# ospi_v14.net
KiCad netlist of a schematic drawn in EAGLE
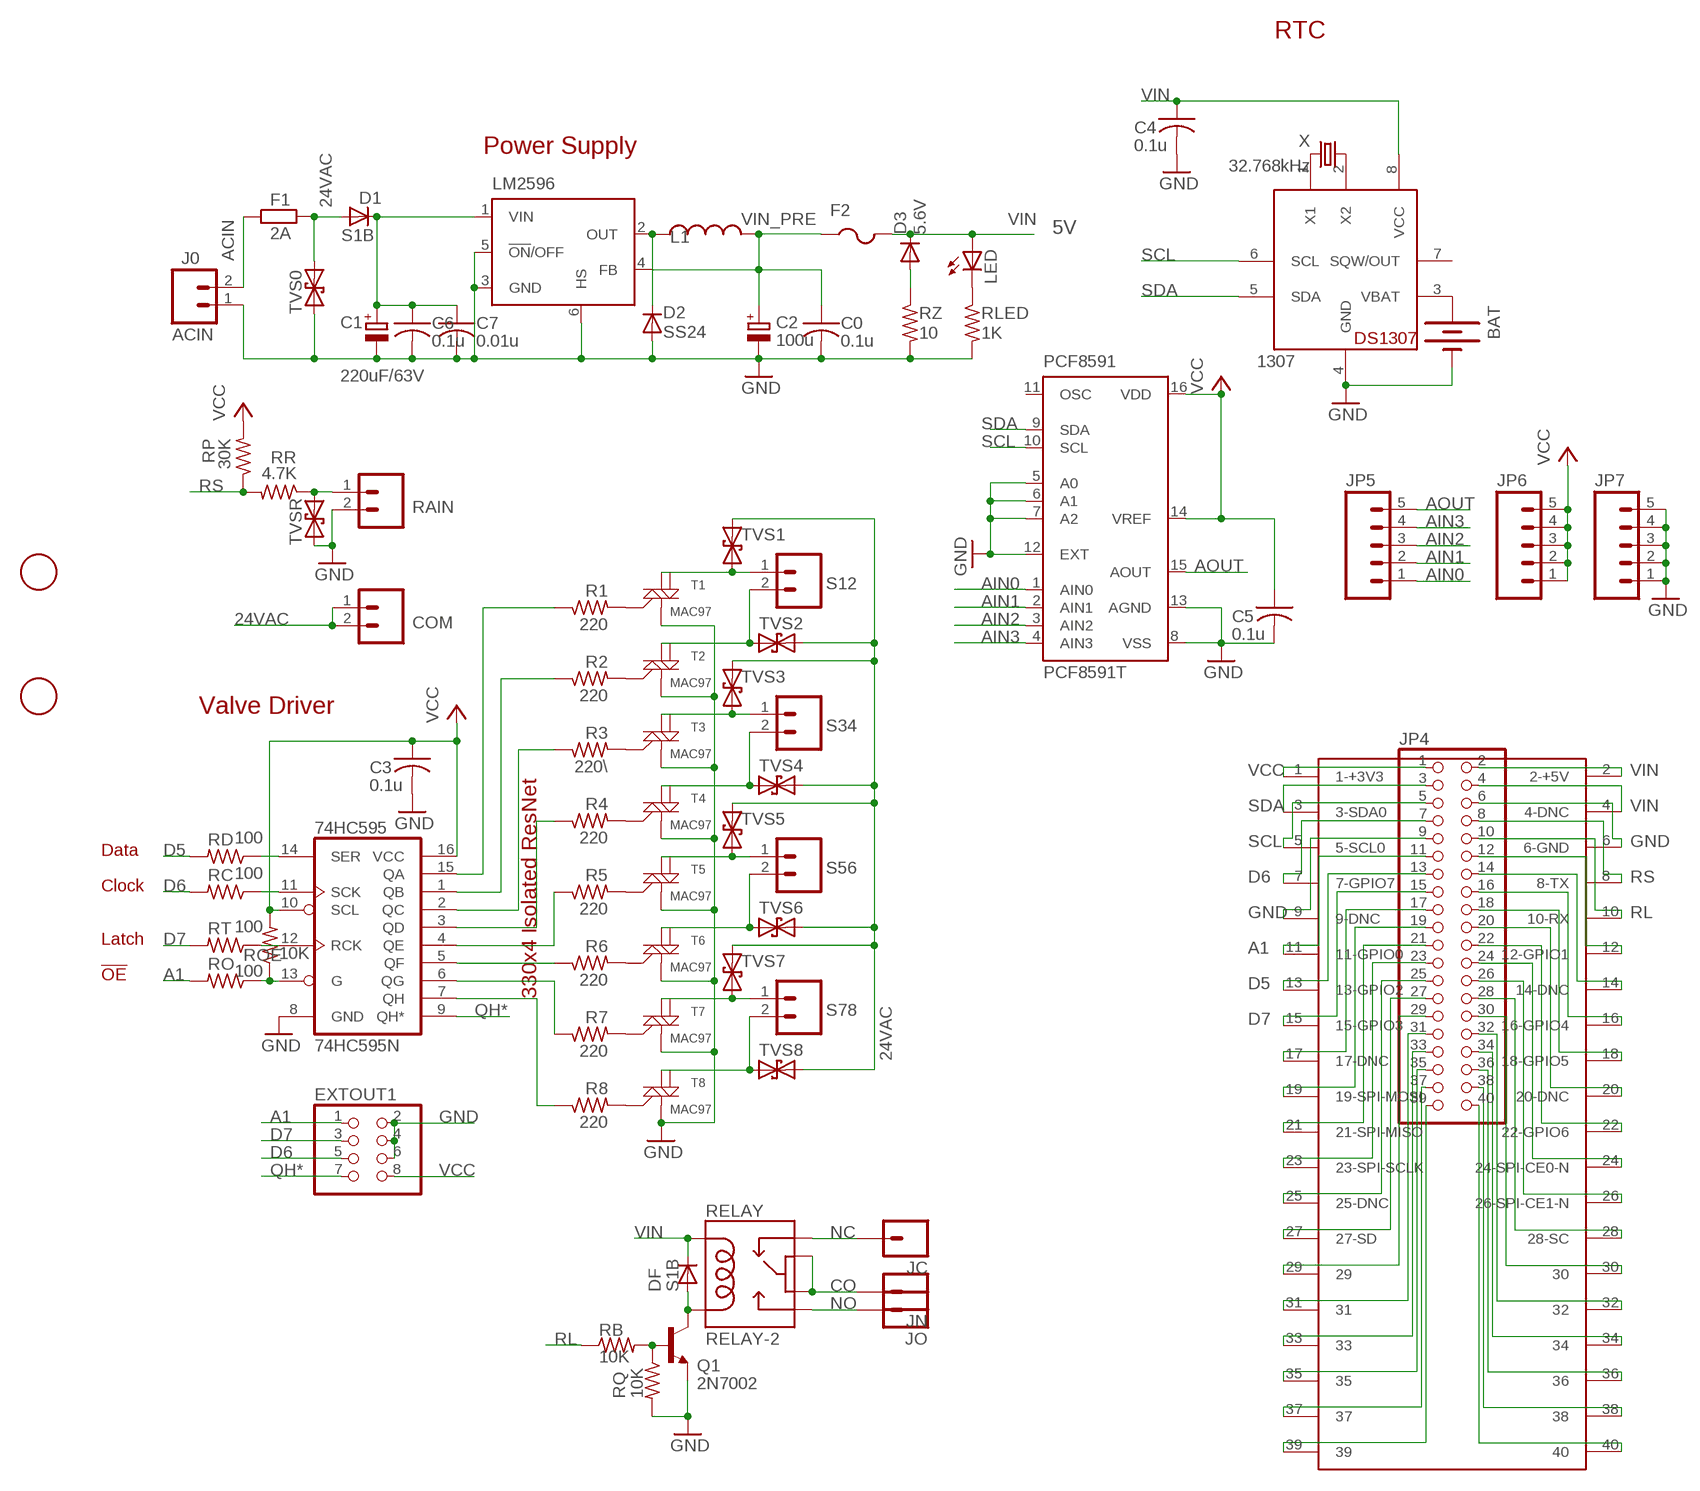
[diagram p0: schematic, sheet 1]

(export (version "E")
  (design (tool "Eeschema 10.0.6"))
  (components
    (comp (ref "74HC595")
      (value "74HC595N")
      (footprint "eagle-import:SO16")
      (libsource (lib "eagle-import") (part "74595DLS"))
    )
    (comp (ref "1307")
      (value "DS1307")
      (footprint "eagle-import:SO08")
      (libsource (lib "eagle-import") (part "DS1307SOIC"))
    )
    (comp (ref "BAT")
      (value "BATTERYBATTERY_12MM_SMT")
      (footprint "eagle-import:BATTCON_12MM_SMT")
      (libsource (lib "eagle-import") (part "BATTERYBATTERY_12MM_SMT"))
    )
    (comp (ref "C0")
      (value "0.1u")
      (footprint "eagle-import:C0805K")
      (libsource (lib "eagle-import") (part "C-USC0805K"))
    )
    (comp (ref "C1")
      (value "220uF/63V")
      (footprint "eagle-import:E3,5-8")
      (libsource (lib "eagle-import") (part "CPOL-EUE3.5-8"))
    )
    (comp (ref "C2")
      (value "100u")
      (footprint "eagle-import:E3,5-8")
      (libsource (lib "eagle-import") (part "CPOL-EUE3.5-8"))
    )
    (comp (ref "C3")
      (value "0.1u")
      (footprint "eagle-import:C0805K")
      (libsource (lib "eagle-import") (part "C-USC0805K"))
    )
    (comp (ref "C4")
      (value "0.1u")
      (footprint "eagle-import:C0805K")
      (libsource (lib "eagle-import") (part "C-USC0805K"))
    )
    (comp (ref "C5")
      (value "0.1u")
      (footprint "eagle-import:C0805K")
      (libsource (lib "eagle-import") (part "C-USC0805K"))
    )
    (comp (ref "C6")
      (value "0.1u")
      (footprint "eagle-import:C0805K")
      (libsource (lib "eagle-import") (part "C-USC0805K"))
    )
    (comp (ref "C7")
      (value "0.01u")
      (footprint "eagle-import:C0805K")
      (libsource (lib "eagle-import") (part "C-USC0805K"))
    )
    (comp (ref "COM")
      (value "M025MM-X")
      (footprint "eagle-import:SCREWTERMINAL-5MM-2-X")
      (libsource (lib "eagle-import") (part "M025MM-X"))
    )
    (comp (ref "D1")
      (value "S1B")
      (footprint "eagle-import:DO-214AC")
      (libsource (lib "eagle-import") (part "DIODE-DO-214AC"))
    )
    (comp (ref "D2")
      (value "SS24")
      (footprint "eagle-import:SMB")
      (libsource (lib "eagle-import") (part "DIODE-SMB"))
    )
    (comp (ref "D3")
      (value "5.6V")
      (footprint "eagle-import:MINIMELF")
      (libsource (lib "eagle-import") (part "DIODE-MINIMELF"))
    )
    (comp (ref "DF")
      (value "S1B")
      (footprint "eagle-import:DO-214AC")
      (libsource (lib "eagle-import") (part "DIODE-DO-214AC"))
    )
    (comp (ref "EXTOUT1")
      (value "PINHD-2X4/90")
      (footprint "eagle-import:2X04_90")
      (libsource (lib "eagle-import") (part "PINHD-2X4/90"))
    )
    (comp (ref "F1")
      (value "2A")
      (footprint "eagle-import:0414V")
      (libsource (lib "eagle-import") (part "R-EU_0414/5V"))
    )
    (comp (ref "F2")
      (value "PTCFUSE-1812")
      (footprint "eagle-import:1812")
      (libsource (lib "eagle-import") (part "PTCFUSE-1812"))
    )
    (comp (ref "J0")
      (value "ACIN")
      (footprint "eagle-import:SCREWTERMINAL-4MM-2-X")
      (libsource (lib "eagle-import") (part "M024MM-X"))
    )
    (comp (ref "JC")
      (value "M01PTH")
      (footprint "eagle-import:1X01")
      (libsource (lib "eagle-import") (part "M01PTH"))
    )
    (comp (ref "JN")
      (value "M01PTH")
      (footprint "eagle-import:1X01")
      (libsource (lib "eagle-import") (part "M01PTH"))
    )
    (comp (ref "JO")
      (value "M01PTH")
      (footprint "eagle-import:1X01")
      (libsource (lib "eagle-import") (part "M01PTH"))
    )
    (comp (ref "JP4")
      (value "PINHD-2X20")
      (footprint "eagle-import:2X20")
      (libsource (lib "eagle-import") (part "PINHD-2X20"))
    )
    (comp (ref "JP5")
      (value "M05PTH")
      (footprint "eagle-import:1X05")
      (libsource (lib "eagle-import") (part "M05PTH"))
    )
    (comp (ref "JP6")
      (value "M05PTH")
      (footprint "eagle-import:1X05")
      (libsource (lib "eagle-import") (part "M05PTH"))
    )
    (comp (ref "JP7")
      (value "M05PTH")
      (footprint "eagle-import:1X05")
      (libsource (lib "eagle-import") (part "M05PTH"))
    )
    (comp (ref "L1")
      (value "150uH")
      (footprint "eagle-import:0207_7")
      (libsource (lib "eagle-import") (part "L-US0207/7"))
    )
    (comp (ref "LED")
      (value "LEDCHIPLED_0805")
      (footprint "eagle-import:CHIPLED_0805")
      (libsource (lib "eagle-import") (part "LEDCHIPLED_0805"))
    )
    (comp (ref "LM2596")
      (value "LM2596S")
      (footprint "eagle-import:TO263-5")
      (fields (field (name "MF") "NATIONAL SEMICONDUCTOR") (field (name "MPN") "LM2596S-ADJ/NOPB"))
      (libsource (lib "eagle-import") (part "LM2596S"))
    )
    (comp (ref "PCF8591")
      (value "PCF8591T")
      (footprint "eagle-import:SO16W")
      (fields (field (name "MPN") "PCF8591T/2,512"))
      (libsource (lib "eagle-import") (part "PCF8591T"))
    )
    (comp (ref "Q1")
      (value "2N7002")
      (footprint "eagle-import:SOT23-3")
      (libsource (lib "eagle-import") (part "TRANSISTOR_NPNSOT23-3"))
    )
    (comp (ref "R1")
      (value "220")
      (footprint "eagle-import:R0805")
      (libsource (lib "eagle-import") (part "R-US_R0805"))
    )
    (comp (ref "R2")
      (value "220")
      (footprint "eagle-import:R0805")
      (libsource (lib "eagle-import") (part "R-US_R0805"))
    )
    (comp (ref "R3")
      (value "220\\")
      (footprint "eagle-import:R0805")
      (libsource (lib "eagle-import") (part "R-US_R0805"))
    )
    (comp (ref "R4")
      (value "220")
      (footprint "eagle-import:R0805")
      (libsource (lib "eagle-import") (part "R-US_R0805"))
    )
    (comp (ref "R5")
      (value "220")
      (footprint "eagle-import:R0805")
      (libsource (lib "eagle-import") (part "R-US_R0805"))
    )
    (comp (ref "R6")
      (value "220")
      (footprint "eagle-import:R0805")
      (libsource (lib "eagle-import") (part "R-US_R0805"))
    )
    (comp (ref "R7")
      (value "220")
      (footprint "eagle-import:R0805")
      (libsource (lib "eagle-import") (part "R-US_R0805"))
    )
    (comp (ref "R8")
      (value "220")
      (footprint "eagle-import:R0805")
      (libsource (lib "eagle-import") (part "R-US_R0805"))
    )
    (comp (ref "RAIN")
      (value "M025MM-X")
      (footprint "eagle-import:SCREWTERMINAL-5MM-2-X")
      (libsource (lib "eagle-import") (part "M025MM-X"))
    )
    (comp (ref "RB")
      (value "10K")
      (footprint "eagle-import:R0805")
      (libsource (lib "eagle-import") (part "R-US_R0805"))
    )
    (comp (ref "RC")
      (value "100")
      (footprint "eagle-import:R0805")
      (libsource (lib "eagle-import") (part "R-US_R0805"))
    )
    (comp (ref "RD")
      (value "100")
      (footprint "eagle-import:R0805")
      (libsource (lib "eagle-import") (part "R-US_R0805"))
    )
    (comp (ref "RELAY")
      (value "RELAY-2")
      (footprint "eagle-import:RELAY-HK4100F")
      (libsource (lib "eagle-import") (part "RELAY-2"))
    )
    (comp (ref "RLED")
      (value "1K")
      (footprint "eagle-import:R0805")
      (libsource (lib "eagle-import") (part "R-US_R0805"))
    )
    (comp (ref "RO")
      (value "100")
      (footprint "eagle-import:R0805")
      (libsource (lib "eagle-import") (part "R-US_R0805"))
    )
    (comp (ref "ROE")
      (value "10K")
      (footprint "eagle-import:R0805")
      (libsource (lib "eagle-import") (part "R-US_R0805"))
    )
    (comp (ref "RP")
      (value "30K")
      (footprint "eagle-import:R0805")
      (libsource (lib "eagle-import") (part "R-US_R0805"))
    )
    (comp (ref "RQ")
      (value "10K")
      (footprint "eagle-import:R0805")
      (libsource (lib "eagle-import") (part "R-US_R0805"))
    )
    (comp (ref "RR")
      (value "4.7K")
      (footprint "eagle-import:R0805")
      (libsource (lib "eagle-import") (part "R-US_R0805"))
    )
    (comp (ref "RT")
      (value "100")
      (footprint "eagle-import:R0805")
      (libsource (lib "eagle-import") (part "R-US_R0805"))
    )
    (comp (ref "RZ")
      (value "10")
      (footprint "eagle-import:R0805")
      (libsource (lib "eagle-import") (part "R-US_R0805"))
    )
    (comp (ref "S12")
      (value "M025MM-X")
      (footprint "eagle-import:SCREWTERMINAL-5MM-2-X")
      (libsource (lib "eagle-import") (part "M025MM-X"))
    )
    (comp (ref "S34")
      (value "M025MM-X")
      (footprint "eagle-import:SCREWTERMINAL-5MM-2-X")
      (libsource (lib "eagle-import") (part "M025MM-X"))
    )
    (comp (ref "S56")
      (value "M025MM-X")
      (footprint "eagle-import:SCREWTERMINAL-5MM-2-X")
      (libsource (lib "eagle-import") (part "M025MM-X"))
    )
    (comp (ref "S78")
      (value "M025MM-X")
      (footprint "eagle-import:SCREWTERMINAL-5MM-2-X")
      (libsource (lib "eagle-import") (part "M025MM-X"))
    )
    (comp (ref "T1")
      (value "MAC97")
      (footprint "eagle-import:SOT223")
      (libsource (lib "eagle-import") (part "MAC97SOT223"))
    )
    (comp (ref "T2")
      (value "MAC97")
      (footprint "eagle-import:SOT223")
      (libsource (lib "eagle-import") (part "MAC97SOT223"))
    )
    (comp (ref "T3")
      (value "MAC97")
      (footprint "eagle-import:SOT223")
      (libsource (lib "eagle-import") (part "MAC97SOT223"))
    )
    (comp (ref "T4")
      (value "MAC97")
      (footprint "eagle-import:SOT223")
      (libsource (lib "eagle-import") (part "MAC97SOT223"))
    )
    (comp (ref "T5")
      (value "MAC97")
      (footprint "eagle-import:SOT223")
      (libsource (lib "eagle-import") (part "MAC97SOT223"))
    )
    (comp (ref "T6")
      (value "MAC97")
      (footprint "eagle-import:SOT223")
      (libsource (lib "eagle-import") (part "MAC97SOT223"))
    )
    (comp (ref "T7")
      (value "MAC97")
      (footprint "eagle-import:SOT223")
      (libsource (lib "eagle-import") (part "MAC97SOT223"))
    )
    (comp (ref "T8")
      (value "MAC97")
      (footprint "eagle-import:SOT223")
      (libsource (lib "eagle-import") (part "MAC97SOT223"))
    )
    (comp (ref "TVS0")
      (value "TVSSMB")
      (footprint "eagle-import:SMB")
      (libsource (lib "eagle-import") (part "TVSSMB"))
    )
    (comp (ref "TVS1")
      (value "TVSSMB")
      (footprint "eagle-import:SMB")
      (libsource (lib "eagle-import") (part "TVSSMB"))
    )
    (comp (ref "TVS2")
      (value "TVSSMB")
      (footprint "eagle-import:SMB")
      (libsource (lib "eagle-import") (part "TVSSMB"))
    )
    (comp (ref "TVS3")
      (value "TVSSMB")
      (footprint "eagle-import:SMB")
      (libsource (lib "eagle-import") (part "TVSSMB"))
    )
    (comp (ref "TVS4")
      (value "TVSSMB")
      (footprint "eagle-import:SMB")
      (libsource (lib "eagle-import") (part "TVSSMB"))
    )
    (comp (ref "TVS5")
      (value "TVSSMB")
      (footprint "eagle-import:SMB")
      (libsource (lib "eagle-import") (part "TVSSMB"))
    )
    (comp (ref "TVS6")
      (value "TVSSMB")
      (footprint "eagle-import:SMB")
      (libsource (lib "eagle-import") (part "TVSSMB"))
    )
    (comp (ref "TVS7")
      (value "TVSSMB")
      (footprint "eagle-import:SMB")
      (libsource (lib "eagle-import") (part "TVSSMB"))
    )
    (comp (ref "TVS8")
      (value "TVSSMB")
      (footprint "eagle-import:SMB")
      (libsource (lib "eagle-import") (part "TVSSMB"))
    )
    (comp (ref "TVSR")
      (value "TVSSMB")
      (footprint "eagle-import:SMB")
      (libsource (lib "eagle-import") (part "TVSSMB"))
    )
    (comp (ref "U$1")
      (value "FIDUCIAL")
      (footprint "eagle-import:FIDUCIAL_1MM")
      (libsource (lib "eagle-import") (part "FIDUCIAL"))
    )
    (comp (ref "U$2")
      (value "RPIB+")
      (footprint "eagle-import:RPIB+")
      (libsource (lib "eagle-import") (part "RPIB+"))
    )
    (comp (ref "U$3")
      (value "FIDUCIAL")
      (footprint "eagle-import:FIDUCIAL_1MM")
      (libsource (lib "eagle-import") (part "FIDUCIAL"))
    )
    (comp (ref "X")
      (value "32.768kHz")
      (footprint "eagle-import:TC38H")
      (libsource (lib "eagle-import") (part "CRYSTALTC38H"))
    )
  )
  (nets
    (net (code "1") (name "/24VAC") (class "Default")
      (node (ref "COM") (pin "1") (pinfunction "1_1") (pintype "passive"))
      (node (ref "COM") (pin "2") (pinfunction "2_2") (pintype "passive"))
      (node (ref "D1") (pin "A") (pinfunction "A_A") (pintype "passive"))
      (node (ref "F1") (pin "2") (pinfunction "2_2") (pintype "passive"))
      (node (ref "TVS0") (pin "C") (pinfunction "C_C") (pintype "passive"))
      (node (ref "TVS1") (pin "C") (pinfunction "C_C") (pintype "passive"))
      (node (ref "TVS2") (pin "C") (pinfunction "C_C") (pintype "passive"))
      (node (ref "TVS3") (pin "C") (pinfunction "C_C") (pintype "passive"))
      (node (ref "TVS4") (pin "C") (pinfunction "C_C") (pintype "passive"))
      (node (ref "TVS5") (pin "C") (pinfunction "C_C") (pintype "passive"))
      (node (ref "TVS6") (pin "C") (pinfunction "C_C") (pintype "passive"))
      (node (ref "TVS7") (pin "C") (pinfunction "C_C") (pintype "passive"))
      (node (ref "TVS8") (pin "C") (pinfunction "C_C") (pintype "passive"))
    )
    (net (code "2") (name "/A1") (class "Default")
      (node (ref "EXTOUT1") (pin "1") (pinfunction "1_1") (pintype "passive"))
      (node (ref "JP4") (pin "11") (pinfunction "11_11") (pintype "passive"))
      (node (ref "RO") (pin "2") (pinfunction "2_2") (pintype "passive"))
      (node (ref "U$2") (pin "11") (pinfunction "11-GPIO0_11") (pintype "bidirectional"))
    )
    (net (code "3") (name "/ACIN") (class "Default")
      (node (ref "F1") (pin "1") (pinfunction "1_1") (pintype "passive"))
      (node (ref "J0") (pin "2") (pinfunction "2_2") (pintype "passive"))
    )
    (net (code "4") (name "/AIN0") (class "Default")
      (node (ref "JP5") (pin "1") (pinfunction "1_1") (pintype "passive"))
      (node (ref "PCF8591") (pin "1") (pinfunction "AIN0_1") (pintype "input"))
    )
    (net (code "5") (name "/AIN1") (class "Default")
      (node (ref "JP5") (pin "2") (pinfunction "2_2") (pintype "passive"))
      (node (ref "PCF8591") (pin "2") (pinfunction "AIN1_2") (pintype "input"))
    )
    (net (code "6") (name "/AIN2") (class "Default")
      (node (ref "JP5") (pin "3") (pinfunction "3_3") (pintype "passive"))
      (node (ref "PCF8591") (pin "3") (pinfunction "AIN2_3") (pintype "input"))
    )
    (net (code "7") (name "/AIN3") (class "Default")
      (node (ref "JP5") (pin "4") (pinfunction "4_4") (pintype "passive"))
      (node (ref "PCF8591") (pin "4") (pinfunction "AIN3_4") (pintype "input"))
    )
    (net (code "8") (name "/AOUT") (class "Default")
      (node (ref "JP5") (pin "5") (pinfunction "5_5") (pintype "passive"))
      (node (ref "PCF8591") (pin "15") (pinfunction "AOUT_15") (pintype "output"))
    )
    (net (code "9") (name "/CO") (class "Default")
      (node (ref "JN") (pin "1") (pinfunction "1_1") (pintype "passive"))
      (node (ref "RELAY") (pin "5") (pinfunction "5_5") (pintype "bidirectional"))
      (node (ref "RELAY") (pin "6") (pinfunction "6_6") (pintype "bidirectional"))
    )
    (net (code "10") (name "/D5") (class "Default")
      (node (ref "JP4") (pin "13") (pinfunction "13_13") (pintype "passive"))
      (node (ref "RD") (pin "2") (pinfunction "2_2") (pintype "passive"))
      (node (ref "U$2") (pin "13") (pinfunction "13-GPIO2_13") (pintype "bidirectional"))
    )
    (net (code "11") (name "/D6") (class "Default")
      (node (ref "EXTOUT1") (pin "5") (pinfunction "5_5") (pintype "passive"))
      (node (ref "JP4") (pin "7") (pinfunction "7_7") (pintype "passive"))
      (node (ref "RC") (pin "2") (pinfunction "2_2") (pintype "passive"))
      (node (ref "U$2") (pin "7") (pinfunction "7-GPIO7_7") (pintype "bidirectional"))
    )
    (net (code "12") (name "/D7") (class "Default")
      (node (ref "EXTOUT1") (pin "3") (pinfunction "3_3") (pintype "passive"))
      (node (ref "JP4") (pin "15") (pinfunction "15_15") (pintype "passive"))
      (node (ref "RT") (pin "2") (pinfunction "2_2") (pintype "passive"))
      (node (ref "U$2") (pin "15") (pinfunction "15-GPIO3_15") (pintype "bidirectional"))
    )
    (net (code "13") (name "/NC") (class "Default")
      (node (ref "JC") (pin "1") (pinfunction "1_1") (pintype "passive"))
      (node (ref "RELAY") (pin "1") (pinfunction "1_1") (pintype "bidirectional"))
    )
    (net (code "14") (name "/NO") (class "Default")
      (node (ref "JO") (pin "1") (pinfunction "1_1") (pintype "passive"))
      (node (ref "RELAY") (pin "10") (pinfunction "10_10") (pintype "bidirectional"))
    )
    (net (code "15") (name "/QH*") (class "Default")
      (node (ref "74HC595") (pin "9") (pinfunction "QH*_9") (pintype "tri_state"))
      (node (ref "EXTOUT1") (pin "7") (pinfunction "7_7") (pintype "passive"))
    )
    (net (code "16") (name "/RL") (class "Default")
      (node (ref "JP4") (pin "10") (pinfunction "10_10") (pintype "passive"))
      (node (ref "RB") (pin "1") (pinfunction "1_1") (pintype "passive"))
      (node (ref "U$2") (pin "10") (pinfunction "10-RX_10") (pintype "bidirectional"))
    )
    (net (code "17") (name "/RS") (class "Default")
      (node (ref "JP4") (pin "8") (pinfunction "8_8") (pintype "passive"))
      (node (ref "RP") (pin "1") (pinfunction "1_1") (pintype "passive"))
      (node (ref "RR") (pin "2") (pinfunction "2_2") (pintype "passive"))
      (node (ref "U$2") (pin "8") (pinfunction "8-TX_8") (pintype "bidirectional"))
    )
    (net (code "18") (name "/SCL") (class "Default")
      (node (ref "1307") (pin "6") (pinfunction "SCL_6") (pintype "bidirectional"))
      (node (ref "JP4") (pin "5") (pinfunction "5_5") (pintype "passive"))
      (node (ref "PCF8591") (pin "10") (pinfunction "SCL_10") (pintype "input"))
      (node (ref "U$2") (pin "5") (pinfunction "5-SCL0_5") (pintype "bidirectional"))
    )
    (net (code "19") (name "/SDA") (class "Default")
      (node (ref "1307") (pin "5") (pinfunction "SDA_5") (pintype "bidirectional"))
      (node (ref "JP4") (pin "3") (pinfunction "3_3") (pintype "passive"))
      (node (ref "PCF8591") (pin "9") (pinfunction "SDA_9") (pintype "bidirectional"))
      (node (ref "U$2") (pin "3") (pinfunction "3-SDA0_3") (pintype "bidirectional"))
    )
    (net (code "20") (name "/VIN") (class "Default")
      (node (ref "1307") (pin "8") (pinfunction "VCC_8") (pintype "power_in"))
      (node (ref "C4") (pin "1") (pinfunction "1_1") (pintype "passive"))
      (node (ref "D3") (pin "C") (pinfunction "C_C") (pintype "passive"))
      (node (ref "DF") (pin "C") (pinfunction "C_C") (pintype "passive"))
      (node (ref "F2") (pin "2") (pinfunction "2_2") (pintype "passive"))
      (node (ref "JP4") (pin "2") (pinfunction "2_2") (pintype "passive"))
      (node (ref "JP4") (pin "4") (pinfunction "4_4") (pintype "passive"))
      (node (ref "LED") (pin "A") (pinfunction "A_A") (pintype "passive"))
      (node (ref "RELAY") (pin "2") (pinfunction "2_2") (pintype "bidirectional"))
      (node (ref "U$2") (pin "2") (pinfunction "2-+5V_2") (pintype "bidirectional"))
      (node (ref "U$2") (pin "4") (pinfunction "4-DNC_4") (pintype "bidirectional"))
    )
    (net (code "21") (name "/VIN_PRE") (class "Default")
      (node (ref "C0") (pin "1") (pinfunction "1_1") (pintype "passive"))
      (node (ref "C2") (pin "+") (pinfunction "+_+") (pintype "passive"))
      (node (ref "F2") (pin "1") (pinfunction "1_1") (pintype "passive"))
      (node (ref "L1") (pin "2") (pinfunction "2_2") (pintype "passive"))
      (node (ref "LM2596") (pin "4") (pinfunction "FB_4") (pintype "input"))
    )
    (net (code "22") (name "GND") (class "Default")
      (node (ref "1307") (pin "4") (pinfunction "GND_4") (pintype "power_in"))
      (node (ref "74HC595") (pin "8") (pinfunction "GND_8") (pintype "power_in"))
      (node (ref "BAT") (pin "P$1") (pinfunction "-_P$1") (pintype "power_in"))
      (node (ref "C0") (pin "2") (pinfunction "2_2") (pintype "passive"))
      (node (ref "C1") (pin "-") (pinfunction "-_-") (pintype "passive"))
      (node (ref "C2") (pin "-") (pinfunction "-_-") (pintype "passive"))
      (node (ref "C3") (pin "2") (pinfunction "2_2") (pintype "passive"))
      (node (ref "C4") (pin "2") (pinfunction "2_2") (pintype "passive"))
      (node (ref "C5") (pin "2") (pinfunction "2_2") (pintype "passive"))
      (node (ref "C6") (pin "2") (pinfunction "2_2") (pintype "passive"))
      (node (ref "C7") (pin "2") (pinfunction "2_2") (pintype "passive"))
      (node (ref "D2") (pin "A") (pinfunction "A_A") (pintype "passive"))
      (node (ref "EXTOUT1") (pin "2") (pinfunction "2_2") (pintype "passive"))
      (node (ref "EXTOUT1") (pin "4") (pinfunction "4_4") (pintype "passive"))
      (node (ref "EXTOUT1") (pin "6") (pinfunction "6_6") (pintype "passive"))
      (node (ref "J0") (pin "1") (pinfunction "1_1") (pintype "passive"))
      (node (ref "JP4") (pin "6") (pinfunction "6_6") (pintype "passive"))
      (node (ref "JP4") (pin "9") (pinfunction "9_9") (pintype "passive"))
      (node (ref "JP7") (pin "1") (pinfunction "1_1") (pintype "passive"))
      (node (ref "JP7") (pin "2") (pinfunction "2_2") (pintype "passive"))
      (node (ref "JP7") (pin "3") (pinfunction "3_3") (pintype "passive"))
      (node (ref "JP7") (pin "4") (pinfunction "4_4") (pintype "passive"))
      (node (ref "JP7") (pin "5") (pinfunction "5_5") (pintype "passive"))
      (node (ref "LM2596") (pin "3") (pinfunction "GND_3") (pintype "power_in"))
      (node (ref "LM2596") (pin "5") (pinfunction "~{ON}/OFF_5") (pintype "input"))
      (node (ref "LM2596") (pin "6") (pinfunction "HS_6") (pintype "power_in"))
      (node (ref "PCF8591") (pin "12") (pinfunction "EXT_12") (pintype "input"))
      (node (ref "PCF8591") (pin "13") (pinfunction "AGND_13") (pintype "power_in"))
      (node (ref "PCF8591") (pin "5") (pinfunction "A0_5") (pintype "input"))
      (node (ref "PCF8591") (pin "6") (pinfunction "A1_6") (pintype "input"))
      (node (ref "PCF8591") (pin "7") (pinfunction "A2_7") (pintype "input"))
      (node (ref "PCF8591") (pin "8") (pinfunction "VSS_8") (pintype "power_in"))
      (node (ref "Q1") (pin "2") (pinfunction "E_2") (pintype "passive"))
      (node (ref "RAIN") (pin "2") (pinfunction "2_2") (pintype "passive"))
      (node (ref "RLED") (pin "2") (pinfunction "2_2") (pintype "passive"))
      (node (ref "RQ") (pin "2") (pinfunction "2_2") (pintype "passive"))
      (node (ref "RZ") (pin "2") (pinfunction "2_2") (pintype "passive"))
      (node (ref "T1") (pin "1") (pinfunction "M1_1") (pintype "bidirectional"))
      (node (ref "T2") (pin "1") (pinfunction "M1_1") (pintype "bidirectional"))
      (node (ref "T3") (pin "1") (pinfunction "M1_1") (pintype "bidirectional"))
      (node (ref "T4") (pin "1") (pinfunction "M1_1") (pintype "bidirectional"))
      (node (ref "T5") (pin "1") (pinfunction "M1_1") (pintype "bidirectional"))
      (node (ref "T6") (pin "1") (pinfunction "M1_1") (pintype "bidirectional"))
      (node (ref "T7") (pin "1") (pinfunction "M1_1") (pintype "bidirectional"))
      (node (ref "T8") (pin "1") (pinfunction "M1_1") (pintype "bidirectional"))
      (node (ref "TVS0") (pin "A") (pinfunction "A_A") (pintype "passive"))
      (node (ref "TVSR") (pin "A") (pinfunction "A_A") (pintype "passive"))
      (node (ref "U$2") (pin "6") (pinfunction "6-GND_6") (pintype "bidirectional"))
      (node (ref "U$2") (pin "9") (pinfunction "9-DNC_9") (pintype "bidirectional"))
    )
    (net (code "23") (name "Net-(74HC595-G)") (class "Default")
      (node (ref "74HC595") (pin "13") (pinfunction "G_13") (pintype "input"))
      (node (ref "RO") (pin "1") (pinfunction "1_1") (pintype "passive"))
      (node (ref "ROE") (pin "1") (pinfunction "1_1") (pintype "passive"))
    )
    (net (code "24") (name "Net-(74HC595-QA)") (class "Default")
      (node (ref "74HC595") (pin "15") (pinfunction "QA_15") (pintype "tri_state"))
      (node (ref "R1") (pin "1") (pinfunction "1_1") (pintype "passive"))
    )
    (net (code "25") (name "Net-(74HC595-QB)") (class "Default")
      (node (ref "74HC595") (pin "1") (pinfunction "QB_1") (pintype "tri_state"))
      (node (ref "R2") (pin "1") (pinfunction "1_1") (pintype "passive"))
    )
    (net (code "26") (name "Net-(74HC595-QC)") (class "Default")
      (node (ref "74HC595") (pin "2") (pinfunction "QC_2") (pintype "tri_state"))
      (node (ref "R3") (pin "1") (pinfunction "1_1") (pintype "passive"))
    )
    (net (code "27") (name "Net-(74HC595-QD)") (class "Default")
      (node (ref "74HC595") (pin "3") (pinfunction "QD_3") (pintype "tri_state"))
      (node (ref "R4") (pin "1") (pinfunction "1_1") (pintype "passive"))
    )
    (net (code "28") (name "Net-(74HC595-QE)") (class "Default")
      (node (ref "74HC595") (pin "4") (pinfunction "QE_4") (pintype "tri_state"))
      (node (ref "R5") (pin "1") (pinfunction "1_1") (pintype "passive"))
    )
    (net (code "29") (name "Net-(74HC595-QF)") (class "Default")
      (node (ref "74HC595") (pin "5") (pinfunction "QF_5") (pintype "tri_state"))
      (node (ref "R6") (pin "1") (pinfunction "1_1") (pintype "passive"))
    )
    (net (code "30") (name "Net-(74HC595-QG)") (class "Default")
      (node (ref "74HC595") (pin "6") (pinfunction "QG_6") (pintype "tri_state"))
      (node (ref "R7") (pin "1") (pinfunction "1_1") (pintype "passive"))
    )
    (net (code "31") (name "Net-(74HC595-QH)") (class "Default")
      (node (ref "74HC595") (pin "7") (pinfunction "QH_7") (pintype "tri_state"))
      (node (ref "R8") (pin "1") (pinfunction "1_1") (pintype "passive"))
    )
    (net (code "32") (name "Net-(74HC595-RCK)") (class "Default")
      (node (ref "74HC595") (pin "12") (pinfunction "RCK_12") (pintype "input"))
      (node (ref "RT") (pin "1") (pinfunction "1_1") (pintype "passive"))
    )
    (net (code "33") (name "Net-(74HC595-SCK)") (class "Default")
      (node (ref "74HC595") (pin "11") (pinfunction "SCK_11") (pintype "input"))
      (node (ref "RC") (pin "1") (pinfunction "1_1") (pintype "passive"))
    )
    (net (code "34") (name "Net-(74HC595-SER)") (class "Default")
      (node (ref "74HC595") (pin "14") (pinfunction "SER_14") (pintype "input"))
      (node (ref "RD") (pin "1") (pinfunction "1_1") (pintype "passive"))
    )
    (net (code "35") (name "Net-(1307-VBAT)") (class "Default")
      (node (ref "1307") (pin "3") (pinfunction "VBAT_3") (pintype "power_in"))
      (node (ref "BAT") (pin "P$2") (pinfunction "+_P$2") (pintype "power_in"))
    )
    (net (code "36") (name "Net-(1307-X1)") (class "Default")
      (node (ref "1307") (pin "1") (pinfunction "X1_1") (pintype "passive"))
      (node (ref "X") (pin "2") (pinfunction "2_2") (pintype "passive"))
    )
    (net (code "37") (name "Net-(1307-X2)") (class "Default")
      (node (ref "1307") (pin "2") (pinfunction "X2_2") (pintype "passive"))
      (node (ref "X") (pin "1") (pinfunction "1_1") (pintype "passive"))
    )
    (net (code "38") (name "Net-(D3-PadA)") (class "Default")
      (node (ref "D3") (pin "A") (pinfunction "A_A") (pintype "passive"))
      (node (ref "RZ") (pin "1") (pinfunction "1_1") (pintype "passive"))
    )
    (net (code "39") (name "Net-(JP4-Pad29)") (class "Default")
      (node (ref "JP4") (pin "29") (pinfunction "29_29") (pintype "passive"))
      (node (ref "U$2") (pin "29") (pinfunction "29_29") (pintype "bidirectional"))
    )
    (net (code "40") (name "Net-(JP4-Pad30)") (class "Default")
      (node (ref "JP4") (pin "30") (pinfunction "30_30") (pintype "passive"))
      (node (ref "U$2") (pin "30") (pinfunction "30_30") (pintype "bidirectional"))
    )
    (net (code "41") (name "Net-(JP4-Pad31)") (class "Default")
      (node (ref "JP4") (pin "31") (pinfunction "31_31") (pintype "passive"))
      (node (ref "U$2") (pin "31") (pinfunction "31_31") (pintype "bidirectional"))
    )
    (net (code "42") (name "Net-(JP4-Pad32)") (class "Default")
      (node (ref "JP4") (pin "32") (pinfunction "32_32") (pintype "passive"))
      (node (ref "U$2") (pin "32") (pinfunction "32_32") (pintype "bidirectional"))
    )
    (net (code "43") (name "Net-(JP4-Pad33)") (class "Default")
      (node (ref "JP4") (pin "33") (pinfunction "33_33") (pintype "passive"))
      (node (ref "U$2") (pin "33") (pinfunction "33_33") (pintype "bidirectional"))
    )
    (net (code "44") (name "Net-(JP4-Pad34)") (class "Default")
      (node (ref "JP4") (pin "34") (pinfunction "34_34") (pintype "passive"))
      (node (ref "U$2") (pin "34") (pinfunction "34_34") (pintype "bidirectional"))
    )
    (net (code "45") (name "Net-(JP4-Pad35)") (class "Default")
      (node (ref "JP4") (pin "35") (pinfunction "35_35") (pintype "passive"))
      (node (ref "U$2") (pin "35") (pinfunction "35_35") (pintype "bidirectional"))
    )
    (net (code "46") (name "Net-(JP4-Pad36)") (class "Default")
      (node (ref "JP4") (pin "36") (pinfunction "36_36") (pintype "passive"))
      (node (ref "U$2") (pin "36") (pinfunction "36_36") (pintype "bidirectional"))
    )
    (net (code "47") (name "Net-(JP4-Pad37)") (class "Default")
      (node (ref "JP4") (pin "37") (pinfunction "37_37") (pintype "passive"))
      (node (ref "U$2") (pin "37") (pinfunction "37_37") (pintype "bidirectional"))
    )
    (net (code "48") (name "Net-(JP4-Pad38)") (class "Default")
      (node (ref "JP4") (pin "38") (pinfunction "38_38") (pintype "passive"))
      (node (ref "U$2") (pin "38") (pinfunction "38_38") (pintype "bidirectional"))
    )
    (net (code "49") (name "Net-(JP4-Pad39)") (class "Default")
      (node (ref "JP4") (pin "39") (pinfunction "39_39") (pintype "passive"))
      (node (ref "U$2") (pin "39") (pinfunction "39_39") (pintype "bidirectional"))
    )
    (net (code "50") (name "Net-(JP4-Pad40)") (class "Default")
      (node (ref "JP4") (pin "40") (pinfunction "40_40") (pintype "passive"))
      (node (ref "U$2") (pin "40") (pinfunction "40_40") (pintype "bidirectional"))
    )
    (net (code "51") (name "Net-(LED-PadC)") (class "Default")
      (node (ref "LED") (pin "C") (pinfunction "C_C") (pintype "passive"))
      (node (ref "RLED") (pin "1") (pinfunction "1_1") (pintype "passive"))
    )
    (net (code "52") (name "Net-(LM2596-OUT)") (class "Default")
      (node (ref "D2") (pin "C") (pinfunction "C_C") (pintype "passive"))
      (node (ref "L1") (pin "1") (pinfunction "1_1") (pintype "passive"))
      (node (ref "LM2596") (pin "2") (pinfunction "OUT_2") (pintype "output"))
    )
    (net (code "53") (name "Net-(LM2596-VIN)") (class "Default")
      (node (ref "C1") (pin "+") (pinfunction "+_+") (pintype "passive"))
      (node (ref "C6") (pin "1") (pinfunction "1_1") (pintype "passive"))
      (node (ref "C7") (pin "1") (pinfunction "1_1") (pintype "passive"))
      (node (ref "D1") (pin "C") (pinfunction "C_C") (pintype "passive"))
      (node (ref "LM2596") (pin "1") (pinfunction "VIN_1") (pintype "input"))
    )
    (net (code "54") (name "Net-(Q1-B)") (class "Default")
      (node (ref "Q1") (pin "1") (pinfunction "B_1") (pintype "passive"))
      (node (ref "RB") (pin "2") (pinfunction "2_2") (pintype "passive"))
      (node (ref "RQ") (pin "1") (pinfunction "1_1") (pintype "passive"))
    )
    (net (code "55") (name "Net-(Q1-C)") (class "Default")
      (node (ref "DF") (pin "A") (pinfunction "A_A") (pintype "passive"))
      (node (ref "Q1") (pin "3") (pinfunction "C_3") (pintype "passive"))
      (node (ref "RELAY") (pin "9") (pinfunction "9_9") (pintype "bidirectional"))
    )
    (net (code "56") (name "Net-(RAIN-Pad1)") (class "Default")
      (node (ref "RAIN") (pin "1") (pinfunction "1_1") (pintype "passive"))
      (node (ref "RR") (pin "1") (pinfunction "1_1") (pintype "passive"))
      (node (ref "TVSR") (pin "C") (pinfunction "C_C") (pintype "passive"))
    )
    (net (code "57") (name "Net-(T1-G)") (class "Default")
      (node (ref "R1") (pin "2") (pinfunction "2_2") (pintype "passive"))
      (node (ref "T1") (pin "3") (pinfunction "G_3") (pintype "bidirectional"))
    )
    (net (code "58") (name "Net-(T1-M2)") (class "Default")
      (node (ref "S12") (pin "1") (pinfunction "1_1") (pintype "passive"))
      (node (ref "T1") (pin "2") (pinfunction "M2_2") (pintype "bidirectional"))
      (node (ref "TVS1") (pin "A") (pinfunction "A_A") (pintype "passive"))
    )
    (net (code "59") (name "Net-(T2-G)") (class "Default")
      (node (ref "R2") (pin "2") (pinfunction "2_2") (pintype "passive"))
      (node (ref "T2") (pin "3") (pinfunction "G_3") (pintype "bidirectional"))
    )
    (net (code "60") (name "Net-(T2-M2)") (class "Default")
      (node (ref "S12") (pin "2") (pinfunction "2_2") (pintype "passive"))
      (node (ref "T2") (pin "2") (pinfunction "M2_2") (pintype "bidirectional"))
      (node (ref "TVS2") (pin "A") (pinfunction "A_A") (pintype "passive"))
    )
    (net (code "61") (name "Net-(T3-G)") (class "Default")
      (node (ref "R3") (pin "2") (pinfunction "2_2") (pintype "passive"))
      (node (ref "T3") (pin "3") (pinfunction "G_3") (pintype "bidirectional"))
    )
    (net (code "62") (name "Net-(T3-M2)") (class "Default")
      (node (ref "S34") (pin "1") (pinfunction "1_1") (pintype "passive"))
      (node (ref "T3") (pin "2") (pinfunction "M2_2") (pintype "bidirectional"))
      (node (ref "TVS3") (pin "A") (pinfunction "A_A") (pintype "passive"))
    )
    (net (code "63") (name "Net-(T4-G)") (class "Default")
      (node (ref "R4") (pin "2") (pinfunction "2_2") (pintype "passive"))
      (node (ref "T4") (pin "3") (pinfunction "G_3") (pintype "bidirectional"))
    )
    (net (code "64") (name "Net-(T4-M2)") (class "Default")
      (node (ref "S34") (pin "2") (pinfunction "2_2") (pintype "passive"))
      (node (ref "T4") (pin "2") (pinfunction "M2_2") (pintype "bidirectional"))
      (node (ref "TVS4") (pin "A") (pinfunction "A_A") (pintype "passive"))
    )
    (net (code "65") (name "Net-(T5-G)") (class "Default")
      (node (ref "R5") (pin "2") (pinfunction "2_2") (pintype "passive"))
      (node (ref "T5") (pin "3") (pinfunction "G_3") (pintype "bidirectional"))
    )
    (net (code "66") (name "Net-(T5-M2)") (class "Default")
      (node (ref "S56") (pin "1") (pinfunction "1_1") (pintype "passive"))
      (node (ref "T5") (pin "2") (pinfunction "M2_2") (pintype "bidirectional"))
      (node (ref "TVS5") (pin "A") (pinfunction "A_A") (pintype "passive"))
    )
    (net (code "67") (name "Net-(T6-G)") (class "Default")
      (node (ref "R6") (pin "2") (pinfunction "2_2") (pintype "passive"))
      (node (ref "T6") (pin "3") (pinfunction "G_3") (pintype "bidirectional"))
    )
    (net (code "68") (name "Net-(T6-M2)") (class "Default")
      (node (ref "S56") (pin "2") (pinfunction "2_2") (pintype "passive"))
      (node (ref "T6") (pin "2") (pinfunction "M2_2") (pintype "bidirectional"))
      (node (ref "TVS6") (pin "A") (pinfunction "A_A") (pintype "passive"))
    )
    (net (code "69") (name "Net-(T7-G)") (class "Default")
      (node (ref "R7") (pin "2") (pinfunction "2_2") (pintype "passive"))
      (node (ref "T7") (pin "3") (pinfunction "G_3") (pintype "bidirectional"))
    )
    (net (code "70") (name "Net-(T7-M2)") (class "Default")
      (node (ref "S78") (pin "1") (pinfunction "1_1") (pintype "passive"))
      (node (ref "T7") (pin "2") (pinfunction "M2_2") (pintype "bidirectional"))
      (node (ref "TVS7") (pin "A") (pinfunction "A_A") (pintype "passive"))
    )
    (net (code "71") (name "Net-(T8-G)") (class "Default")
      (node (ref "R8") (pin "2") (pinfunction "2_2") (pintype "passive"))
      (node (ref "T8") (pin "3") (pinfunction "G_3") (pintype "bidirectional"))
    )
    (net (code "72") (name "Net-(T8-M2)") (class "Default")
      (node (ref "S78") (pin "2") (pinfunction "2_2") (pintype "passive"))
      (node (ref "T8") (pin "2") (pinfunction "M2_2") (pintype "bidirectional"))
      (node (ref "TVS8") (pin "A") (pinfunction "A_A") (pintype "passive"))
    )
    (net (code "73") (name "Net-(U$2-12-GPIO1)") (class "Default")
      (node (ref "JP4") (pin "12") (pinfunction "12_12") (pintype "passive"))
      (node (ref "U$2") (pin "12") (pinfunction "12-GPIO1_12") (pintype "bidirectional"))
    )
    (net (code "74") (name "Net-(U$2-14-DNC)") (class "Default")
      (node (ref "JP4") (pin "14") (pinfunction "14_14") (pintype "passive"))
      (node (ref "U$2") (pin "14") (pinfunction "14-DNC_14") (pintype "bidirectional"))
    )
    (net (code "75") (name "Net-(U$2-16-GPIO4)") (class "Default")
      (node (ref "JP4") (pin "16") (pinfunction "16_16") (pintype "passive"))
      (node (ref "U$2") (pin "16") (pinfunction "16-GPIO4_16") (pintype "bidirectional"))
    )
    (net (code "76") (name "Net-(U$2-17-DNC)") (class "Default")
      (node (ref "JP4") (pin "17") (pinfunction "17_17") (pintype "passive"))
      (node (ref "U$2") (pin "17") (pinfunction "17-DNC_17") (pintype "bidirectional"))
    )
    (net (code "77") (name "Net-(U$2-18-GPIO5)") (class "Default")
      (node (ref "JP4") (pin "18") (pinfunction "18_18") (pintype "passive"))
      (node (ref "U$2") (pin "18") (pinfunction "18-GPIO5_18") (pintype "bidirectional"))
    )
    (net (code "78") (name "Net-(U$2-19-SPI-MOSI)") (class "Default")
      (node (ref "JP4") (pin "19") (pinfunction "19_19") (pintype "passive"))
      (node (ref "U$2") (pin "19") (pinfunction "19-SPI-MOSI_19") (pintype "bidirectional"))
    )
    (net (code "79") (name "Net-(U$2-20-DNC)") (class "Default")
      (node (ref "JP4") (pin "20") (pinfunction "20_20") (pintype "passive"))
      (node (ref "U$2") (pin "20") (pinfunction "20-DNC_20") (pintype "bidirectional"))
    )
    (net (code "80") (name "Net-(U$2-21-SPI-MISO)") (class "Default")
      (node (ref "JP4") (pin "21") (pinfunction "21_21") (pintype "passive"))
      (node (ref "U$2") (pin "21") (pinfunction "21-SPI-MISO_21") (pintype "bidirectional"))
    )
    (net (code "81") (name "Net-(U$2-22-GPIO6)") (class "Default")
      (node (ref "JP4") (pin "22") (pinfunction "22_22") (pintype "passive"))
      (node (ref "U$2") (pin "22") (pinfunction "22-GPIO6_22") (pintype "bidirectional"))
    )
    (net (code "82") (name "Net-(U$2-23-SPI-SCLK)") (class "Default")
      (node (ref "JP4") (pin "23") (pinfunction "23_23") (pintype "passive"))
      (node (ref "U$2") (pin "23") (pinfunction "23-SPI-SCLK_23") (pintype "bidirectional"))
    )
    (net (code "83") (name "Net-(U$2-24-SPI-CE0-N)") (class "Default")
      (node (ref "JP4") (pin "24") (pinfunction "24_24") (pintype "passive"))
      (node (ref "U$2") (pin "24") (pinfunction "24-SPI-CE0-N_24") (pintype "bidirectional"))
    )
    (net (code "84") (name "Net-(U$2-25-DNC)") (class "Default")
      (node (ref "JP4") (pin "25") (pinfunction "25_25") (pintype "passive"))
      (node (ref "U$2") (pin "25") (pinfunction "25-DNC_25") (pintype "bidirectional"))
    )
    (net (code "85") (name "Net-(U$2-26-SPI-CE1-N)") (class "Default")
      (node (ref "JP4") (pin "26") (pinfunction "26_26") (pintype "passive"))
      (node (ref "U$2") (pin "26") (pinfunction "26-SPI-CE1-N_26") (pintype "bidirectional"))
    )
    (net (code "86") (name "Net-(U$2-27-SD)") (class "Default")
      (node (ref "JP4") (pin "27") (pinfunction "27_27") (pintype "passive"))
      (node (ref "U$2") (pin "27") (pinfunction "27-SD_27") (pintype "bidirectional"))
    )
    (net (code "87") (name "Net-(U$2-28-SC)") (class "Default")
      (node (ref "JP4") (pin "28") (pinfunction "28_28") (pintype "passive"))
      (node (ref "U$2") (pin "28") (pinfunction "28-SC_28") (pintype "bidirectional"))
    )
    (net (code "88") (name "VCC") (class "Default")
      (node (ref "74HC595") (pin "10") (pinfunction "SCL_10") (pintype "input"))
      (node (ref "74HC595") (pin "16") (pinfunction "VCC_16") (pintype "power_in"))
      (node (ref "C3") (pin "1") (pinfunction "1_1") (pintype "passive"))
      (node (ref "C5") (pin "1") (pinfunction "1_1") (pintype "passive"))
      (node (ref "EXTOUT1") (pin "8") (pinfunction "8_8") (pintype "passive"))
      (node (ref "JP4") (pin "1") (pinfunction "1_1") (pintype "passive"))
      (node (ref "JP6") (pin "1") (pinfunction "1_1") (pintype "passive"))
      (node (ref "JP6") (pin "2") (pinfunction "2_2") (pintype "passive"))
      (node (ref "JP6") (pin "3") (pinfunction "3_3") (pintype "passive"))
      (node (ref "JP6") (pin "4") (pinfunction "4_4") (pintype "passive"))
      (node (ref "JP6") (pin "5") (pinfunction "5_5") (pintype "passive"))
      (node (ref "PCF8591") (pin "14") (pinfunction "VREF_14") (pintype "input"))
      (node (ref "PCF8591") (pin "16") (pinfunction "VDD_16") (pintype "power_in"))
      (node (ref "ROE") (pin "2") (pinfunction "2_2") (pintype "passive"))
      (node (ref "RP") (pin "2") (pinfunction "2_2") (pintype "passive"))
      (node (ref "U$2") (pin "1") (pinfunction "1-+3V3_1") (pintype "bidirectional"))
    )
    (net (code "89") (name "unconnected-(1307-SQW{slash}OUT-Pad7)") (class "Default")
      (node (ref "1307") (pin "7") (pinfunction "SQW/OUT_7") (pintype "bidirectional"))
    )
    (net (code "90") (name "unconnected-(PCF8591-OSC-Pad11)") (class "Default")
      (node (ref "PCF8591") (pin "11") (pinfunction "OSC_11") (pintype "input"))
    )
    (net (code "91") (name "unconnected-(T1-M2-4-Pad4)") (class "Default")
      (node (ref "T1") (pin "4") (pinfunction "M2-4_4") (pintype "bidirectional"))
    )
    (net (code "92") (name "unconnected-(T2-M2-4-Pad4)") (class "Default")
      (node (ref "T2") (pin "4") (pinfunction "M2-4_4") (pintype "bidirectional"))
    )
    (net (code "93") (name "unconnected-(T3-M2-4-Pad4)") (class "Default")
      (node (ref "T3") (pin "4") (pinfunction "M2-4_4") (pintype "bidirectional"))
    )
    (net (code "94") (name "unconnected-(T4-M2-4-Pad4)") (class "Default")
      (node (ref "T4") (pin "4") (pinfunction "M2-4_4") (pintype "bidirectional"))
    )
    (net (code "95") (name "unconnected-(T5-M2-4-Pad4)") (class "Default")
      (node (ref "T5") (pin "4") (pinfunction "M2-4_4") (pintype "bidirectional"))
    )
    (net (code "96") (name "unconnected-(T6-M2-4-Pad4)") (class "Default")
      (node (ref "T6") (pin "4") (pinfunction "M2-4_4") (pintype "bidirectional"))
    )
    (net (code "97") (name "unconnected-(T7-M2-4-Pad4)") (class "Default")
      (node (ref "T7") (pin "4") (pinfunction "M2-4_4") (pintype "bidirectional"))
    )
    (net (code "98") (name "unconnected-(T8-M2-4-Pad4)") (class "Default")
      (node (ref "T8") (pin "4") (pinfunction "M2-4_4") (pintype "bidirectional"))
    )
  )
)
